# uCAN_Cape.net
KiCad netlist of a schematic drawn in EAGLE
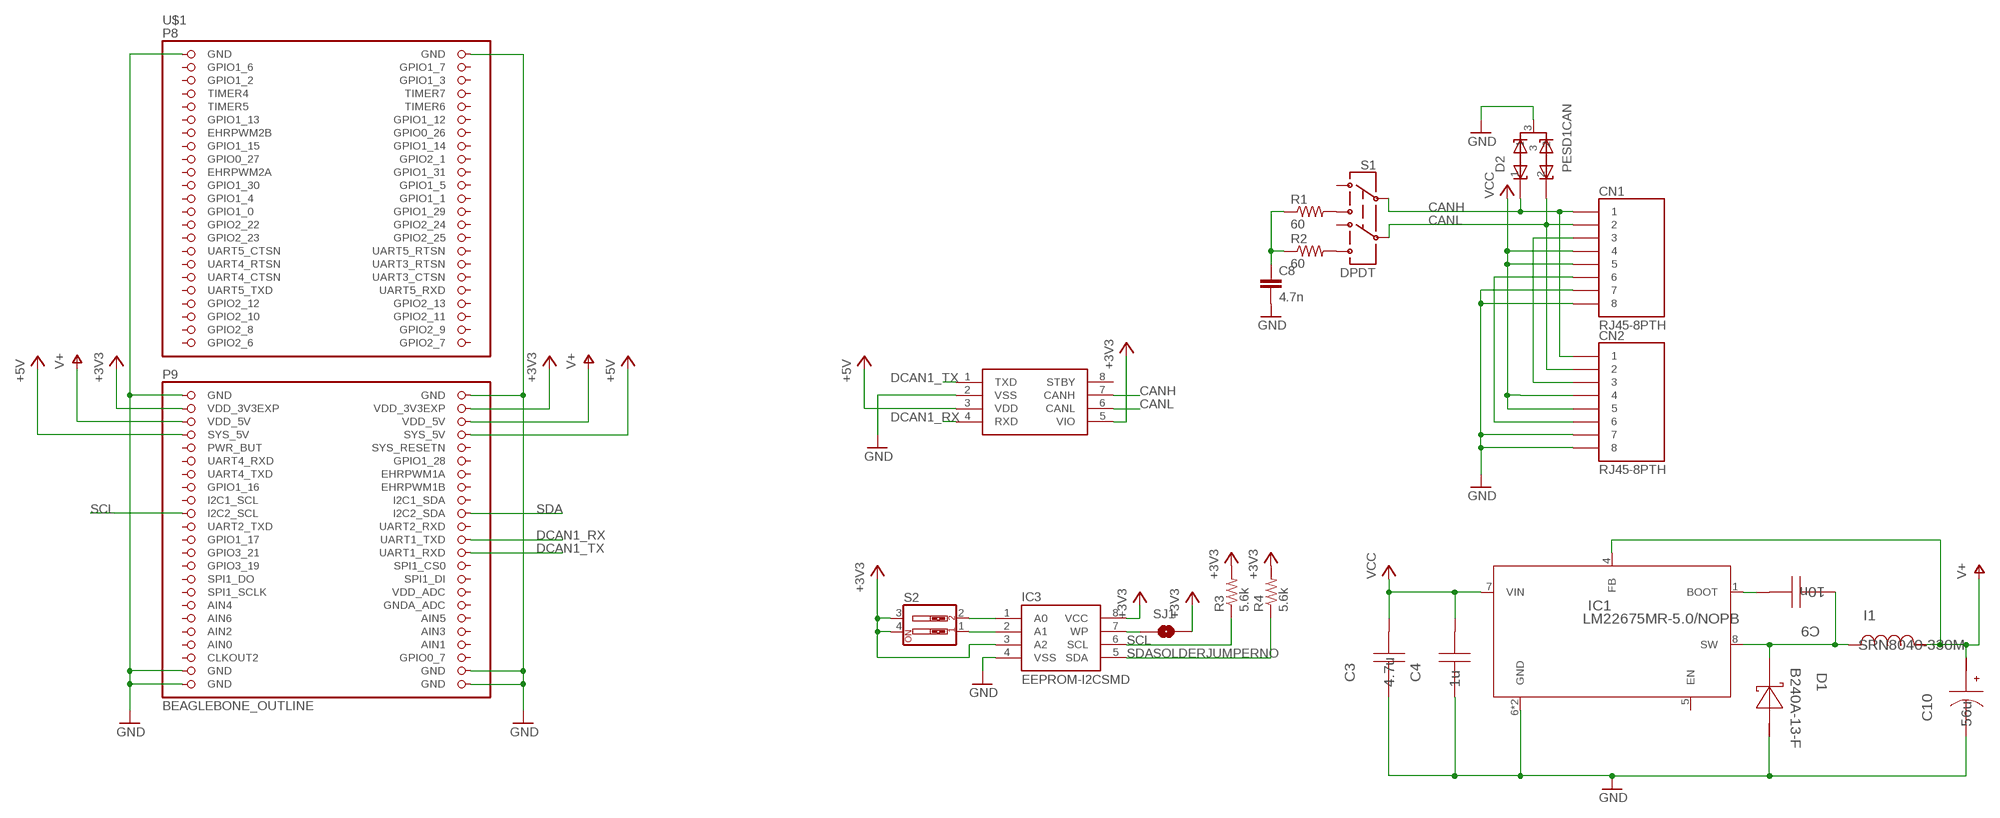
[diagram p0: schematic, sheet 1]

(export (version "E")
  (design (tool "Eeschema 10.0.6"))
  (components
    (comp (ref "C3")
      (value "4.7u")
      (footprint "eagle-import:1206")
      (fields (field (name "MANUFACTURER_PART_NUMBER") "GRM31CR71H475KA12L"))
      (libsource (lib "eagle-import") (part "GRM31CR71H475KA12L"))
    )
    (comp (ref "C4")
      (value "1u")
      (footprint "eagle-import:0805")
      (fields (field (name "MANUFACTURER_PART_NUMBER") "GMK212B7105KG-T"))
      (libsource (lib "eagle-import") (part "GMK212B7105KG-T"))
    )
    (comp (ref "C8")
      (value "4.7n")
      (footprint "eagle-import:0603-CAP")
      (libsource (lib "eagle-import") (part "CAP0603-CAP"))
    )
    (comp (ref "C9")
      (value "10n")
      (footprint "eagle-import:0805")
      (fields (field (name "MANUFACTURER_PART_NUMBER") "C0805C103K5RACTU"))
      (libsource (lib "eagle-import") (part "C0805C103K5RACTU"))
    )
    (comp (ref "C10")
      (value "56u")
      (footprint "eagle-import:SM_RADIAL_6.3AMM")
      (fields (field (name "MANUFACTURER_PART_NUMBER") "10SVP56M"))
      (libsource (lib "eagle-import") (part "10SVP56M"))
    )
    (comp (ref "CN1")
      (value "RJ45-8PTH")
      (footprint "eagle-import:RJ45-8")
      (libsource (lib "eagle-import") (part "RJ45-8PTH"))
    )
    (comp (ref "CN2")
      (value "RJ45-8PTH")
      (footprint "eagle-import:RJ45-8")
      (libsource (lib "eagle-import") (part "RJ45-8PTH"))
    )
    (comp (ref "D1")
      (value "B240A-13-F")
      (footprint "eagle-import:SMA")
      (libsource (lib "eagle-import") (part "B240A-13-F"))
    )
    (comp (ref "D2")
      (value "PESD1CAN")
      (footprint "eagle-import:SOT23")
      (libsource (lib "eagle-import") (part "PESD1CAN"))
    )
    (comp (ref "I1")
      (value "SRN8040-330M")
      (footprint "eagle-import:SRN8040")
      (libsource (lib "eagle-import") (part "SRN8040-330M"))
    )
    (comp (ref "IC1")
      (value "LM22675MR-5.0/NOPB")
      (footprint "eagle-import:MRA08B")
      (libsource (lib "eagle-import") (part "LM22675MR-5.0/NOPB"))
    )
    (comp (ref "IC2")
      (value "MCP2562")
      (footprint "eagle-import:SO08")
      (libsource (lib "eagle-import") (part "MCP2562"))
    )
    (comp (ref "IC3")
      (value "EEPROM-I2CSMD")
      (footprint "eagle-import:SO08")
      (libsource (lib "eagle-import") (part "EEPROM-I2CSMD"))
    )
    (comp (ref "R1")
      (value "60")
      (footprint "eagle-import:0603-RES")
      (libsource (lib "eagle-import") (part "RESISTOR0603-RES"))
    )
    (comp (ref "R2")
      (value "60")
      (footprint "eagle-import:0603-RES")
      (libsource (lib "eagle-import") (part "RESISTOR0603-RES"))
    )
    (comp (ref "R3")
      (value "5.6k")
      (footprint "eagle-import:0603-RES")
      (libsource (lib "eagle-import") (part "RESISTOR0603-RES"))
    )
    (comp (ref "R4")
      (value "5.6k")
      (footprint "eagle-import:0603-RES")
      (libsource (lib "eagle-import") (part "RESISTOR0603-RES"))
    )
    (comp (ref "S1")
      (value "DPDT")
      (footprint "eagle-import:AYZ0202")
      (libsource (lib "eagle-import") (part "SWITCH-DPDTAYZ0202"))
    )
    (comp (ref "S2")
      (value "SW_DIP-2")
      (footprint "eagle-import:DIPSWITCH-02")
      (libsource (lib "eagle-import") (part "SW_DIP-2"))
    )
    (comp (ref "SJ1")
      (value "SOLDERJUMPERNO")
      (footprint "eagle-import:SJ_2S-NO")
      (libsource (lib "eagle-import") (part "SOLDERJUMPERNO"))
    )
    (comp (ref "U$1")
      (value "BEAGLEBONE_OUTLINE")
      (footprint "eagle-import:BEAGLEBONE_SHIELD")
      (libsource (lib "eagle-import") (part "BEAGLEBONE_OUTLINE"))
    )
  )
  (nets
    (net (code "1") (name "+3V3") (class "Default")
      (node (ref "IC2") (pin "5") (pinfunction "VIO_5") (pintype "bidirectional"))
      (node (ref "IC3") (pin "3") (pinfunction "A2_3") (pintype "bidirectional"))
      (node (ref "IC3") (pin "8") (pinfunction "VCC_8") (pintype "power_in"))
      (node (ref "R3") (pin "2") (pinfunction "2_2") (pintype "passive"))
      (node (ref "R4") (pin "2") (pinfunction "2_2") (pintype "passive"))
      (node (ref "S2") (pin "3") (pinfunction "3_3") (pintype "passive"))
      (node (ref "S2") (pin "4") (pinfunction "4_4") (pintype "passive"))
      (node (ref "SJ1") (pin "2") (pinfunction "2_2") (pintype "passive"))
      (node (ref "U$1") (pin "49") (pinfunction "VDD_3V3EXP_49") (pintype "power_in"))
      (node (ref "U$1") (pin "50") (pinfunction "VDD_3V3EXP_50") (pintype "power_in"))
    )
    (net (code "2") (name "+5V") (class "Default")
      (node (ref "IC2") (pin "3") (pinfunction "VDD_3") (pintype "bidirectional"))
      (node (ref "U$1") (pin "53") (pinfunction "SYS_5V_53") (pintype "power_in"))
      (node (ref "U$1") (pin "54") (pinfunction "SYS_5V_54") (pintype "passive"))
    )
    (net (code "3") (name "/AIN0") (class "Default")
      (node (ref "U$1") (pin "85") (pinfunction "AIN0_85") (pintype "power_in"))
    )
    (net (code "4") (name "/CANH") (class "Default")
      (node (ref "CN1") (pin "1") (pinfunction "1_1") (pintype "bidirectional"))
      (node (ref "CN2") (pin "1") (pinfunction "1_1") (pintype "bidirectional"))
      (node (ref "D2") (pin "1") (pinfunction "1_1") (pintype "bidirectional"))
      (node (ref "IC2") (pin "7") (pinfunction "CANH_7") (pintype "bidirectional"))
      (node (ref "S1") (pin "2") (pinfunction "2_2") (pintype "bidirectional"))
    )
    (net (code "5") (name "/CANL") (class "Default")
      (node (ref "CN1") (pin "2") (pinfunction "2_2") (pintype "bidirectional"))
      (node (ref "CN2") (pin "2") (pinfunction "2_2") (pintype "bidirectional"))
      (node (ref "D2") (pin "2") (pinfunction "2_2") (pintype "bidirectional"))
      (node (ref "IC2") (pin "6") (pinfunction "CANL_6") (pintype "bidirectional"))
      (node (ref "S1") (pin "5") (pinfunction "5_5") (pintype "bidirectional"))
    )
    (net (code "6") (name "/DCAN1_RX") (class "Default")
      (node (ref "IC2") (pin "4") (pinfunction "RXD_4") (pintype "bidirectional"))
      (node (ref "U$1") (pin "70") (pinfunction "UART1_TXD_70") (pintype "passive"))
    )
    (net (code "7") (name "/DCAN1_TX") (class "Default")
      (node (ref "IC2") (pin "1") (pinfunction "TXD_1") (pintype "bidirectional"))
      (node (ref "U$1") (pin "72") (pinfunction "UART1_RXD_72") (pintype "passive"))
    )
    (net (code "8") (name "/SCL") (class "Default")
      (node (ref "IC3") (pin "6") (pinfunction "SCL_6") (pintype "bidirectional"))
      (node (ref "R3") (pin "1") (pinfunction "1_1") (pintype "passive"))
      (node (ref "U$1") (pin "65") (pinfunction "I2C2_SCL_65") (pintype "passive"))
    )
    (net (code "9") (name "/SDA") (class "Default")
      (node (ref "IC3") (pin "5") (pinfunction "SDA_5") (pintype "bidirectional"))
      (node (ref "R4") (pin "1") (pinfunction "1_1") (pintype "passive"))
      (node (ref "U$1") (pin "66") (pinfunction "I2C2_SDA_66") (pintype "passive"))
    )
    (net (code "10") (name "GND") (class "Default")
      (node (ref "C10") (pin "2") (pinfunction "-_2") (pintype "passive"))
      (node (ref "C3") (pin "2") (pinfunction "2_2") (pintype "passive"))
      (node (ref "C4") (pin "2") (pinfunction "2_2") (pintype "passive"))
      (node (ref "C8") (pin "2") (pinfunction "2_2") (pintype "passive"))
      (node (ref "CN1") (pin "7") (pinfunction "7_7") (pintype "bidirectional"))
      (node (ref "CN1") (pin "8") (pinfunction "8_8") (pintype "bidirectional"))
      (node (ref "CN2") (pin "7") (pinfunction "7_7") (pintype "bidirectional"))
      (node (ref "CN2") (pin "8") (pinfunction "8_8") (pintype "bidirectional"))
      (node (ref "D1") (pin "2") (pinfunction "A_2") (pintype "passive"))
      (node (ref "D2") (pin "3") (pinfunction "3_3") (pintype "bidirectional"))
      (node (ref "IC1") (pin "6") (pinfunction "GND_6") (pintype "passive"))
      (node (ref "IC1") (pin "EPAD") (pinfunction "GND_EPAD") (pintype "passive"))
      (node (ref "IC2") (pin "2") (pinfunction "VSS_2") (pintype "bidirectional"))
      (node (ref "IC3") (pin "4") (pinfunction "VSS_4") (pintype "power_in"))
      (node (ref "U$1") (pin "1") (pinfunction "GND_1") (pintype "power_in"))
      (node (ref "U$1") (pin "2") (pinfunction "GND_2") (pintype "power_in"))
      (node (ref "U$1") (pin "47") (pinfunction "GND_47") (pintype "power_in"))
      (node (ref "U$1") (pin "48") (pinfunction "GND_48") (pintype "power_in"))
      (node (ref "U$1") (pin "89") (pinfunction "GND_89") (pintype "power_in"))
      (node (ref "U$1") (pin "90") (pinfunction "GND_90") (pintype "power_in"))
      (node (ref "U$1") (pin "91") (pinfunction "GND_91") (pintype "power_in"))
      (node (ref "U$1") (pin "92") (pinfunction "GND_92") (pintype "power_in"))
    )
    (net (code "11") (name "Net-(C8-Pad1)") (class "Default")
      (node (ref "C8") (pin "1") (pinfunction "1_1") (pintype "passive"))
      (node (ref "R1") (pin "1") (pinfunction "1_1") (pintype "passive"))
      (node (ref "R2") (pin "1") (pinfunction "1_1") (pintype "passive"))
    )
    (net (code "12") (name "Net-(CN1-Pad3)") (class "Default")
      (node (ref "CN1") (pin "3") (pinfunction "3_3") (pintype "bidirectional"))
      (node (ref "CN2") (pin "3") (pinfunction "3_3") (pintype "bidirectional"))
    )
    (net (code "13") (name "Net-(CN1-Pad6)") (class "Default")
      (node (ref "CN1") (pin "6") (pinfunction "6_6") (pintype "bidirectional"))
      (node (ref "CN2") (pin "6") (pinfunction "6_6") (pintype "bidirectional"))
    )
    (net (code "14") (name "Net-(D1-K)") (class "Default")
      (node (ref "C9") (pin "2") (pinfunction "2_2") (pintype "passive"))
      (node (ref "D1") (pin "1") (pinfunction "K_1") (pintype "passive"))
      (node (ref "I1") (pin "2") (pinfunction "2_2") (pintype "passive"))
      (node (ref "IC1") (pin "8") (pinfunction "SW_8") (pintype "passive"))
    )
    (net (code "15") (name "Net-(IC1-BOOT)") (class "Default")
      (node (ref "C9") (pin "1") (pinfunction "1_1") (pintype "passive"))
      (node (ref "IC1") (pin "1") (pinfunction "BOOT_1") (pintype "passive"))
    )
    (net (code "16") (name "Net-(IC3-A0)") (class "Default")
      (node (ref "IC3") (pin "1") (pinfunction "A0_1") (pintype "bidirectional"))
      (node (ref "S2") (pin "2") (pinfunction "2_2") (pintype "passive"))
    )
    (net (code "17") (name "Net-(IC3-A1)") (class "Default")
      (node (ref "IC3") (pin "2") (pinfunction "A1_2") (pintype "bidirectional"))
      (node (ref "S2") (pin "1") (pinfunction "1_1") (pintype "passive"))
    )
    (net (code "18") (name "Net-(IC3-WP)") (class "Default")
      (node (ref "IC3") (pin "7") (pinfunction "WP_7") (pintype "bidirectional"))
      (node (ref "SJ1") (pin "1") (pinfunction "1_1") (pintype "passive"))
    )
    (net (code "19") (name "Net-(R1-Pad2)") (class "Default")
      (node (ref "R1") (pin "2") (pinfunction "2_2") (pintype "passive"))
      (node (ref "S1") (pin "3") (pinfunction "3_3") (pintype "bidirectional"))
    )
    (net (code "20") (name "Net-(R2-Pad2)") (class "Default")
      (node (ref "R2") (pin "2") (pinfunction "2_2") (pintype "passive"))
      (node (ref "S1") (pin "6") (pinfunction "6_6") (pintype "bidirectional"))
    )
    (net (code "21") (name "V+") (class "Default")
      (node (ref "C10") (pin "1") (pinfunction "+_1") (pintype "passive"))
      (node (ref "I1") (pin "1") (pinfunction "1_1") (pintype "passive"))
      (node (ref "IC1") (pin "4") (pinfunction "FB_4") (pintype "passive"))
      (node (ref "U$1") (pin "51") (pinfunction "VDD_5V_51") (pintype "power_in"))
      (node (ref "U$1") (pin "52") (pinfunction "VDD_5V_52") (pintype "power_in"))
    )
    (net (code "22") (name "VCC") (class "Default")
      (node (ref "C3") (pin "1") (pinfunction "1_1") (pintype "passive"))
      (node (ref "C4") (pin "1") (pinfunction "1_1") (pintype "passive"))
      (node (ref "CN1") (pin "4") (pinfunction "4_4") (pintype "bidirectional"))
      (node (ref "CN1") (pin "5") (pinfunction "5_5") (pintype "bidirectional"))
      (node (ref "CN2") (pin "4") (pinfunction "4_4") (pintype "bidirectional"))
      (node (ref "CN2") (pin "5") (pinfunction "5_5") (pintype "bidirectional"))
      (node (ref "IC1") (pin "7") (pinfunction "VIN_7") (pintype "passive"))
    )
    (net (code "23") (name "unconnected-(IC1-EN-Pad5)") (class "Default")
      (node (ref "IC1") (pin "5") (pinfunction "EN_5") (pintype "passive"))
    )
    (net (code "24") (name "unconnected-(IC2-STBY-Pad8)") (class "Default")
      (node (ref "IC2") (pin "8") (pinfunction "STBY_8") (pintype "bidirectional"))
    )
    (net (code "25") (name "unconnected-(S1-Pad1)") (class "Default")
      (node (ref "S1") (pin "1") (pinfunction "1_1") (pintype "bidirectional"))
    )
    (net (code "26") (name "unconnected-(S1-Pad4)") (class "Default")
      (node (ref "S1") (pin "4") (pinfunction "4_4") (pintype "bidirectional"))
    )
    (net (code "27") (name "unconnected-(U$1-AIN1-Pad86)") (class "Default")
      (node (ref "U$1") (pin "86") (pinfunction "AIN1_86") (pintype "passive"))
    )
    (net (code "28") (name "unconnected-(U$1-AIN2-Pad83)") (class "Default")
      (node (ref "U$1") (pin "83") (pinfunction "AIN2_83") (pintype "passive"))
    )
    (net (code "29") (name "unconnected-(U$1-AIN3-Pad84)") (class "Default")
      (node (ref "U$1") (pin "84") (pinfunction "AIN3_84") (pintype "passive"))
    )
    (net (code "30") (name "unconnected-(U$1-AIN4-Pad79)") (class "Default")
      (node (ref "U$1") (pin "79") (pinfunction "AIN4_79") (pintype "passive"))
    )
    (net (code "31") (name "unconnected-(U$1-AIN5-Pad82)") (class "Default")
      (node (ref "U$1") (pin "82") (pinfunction "AIN5_82") (pintype "passive"))
    )
    (net (code "32") (name "unconnected-(U$1-AIN6-Pad81)") (class "Default")
      (node (ref "U$1") (pin "81") (pinfunction "AIN6_81") (pintype "passive"))
    )
    (net (code "33") (name "unconnected-(U$1-CLKOUT2-Pad87)") (class "Default")
      (node (ref "U$1") (pin "87") (pinfunction "CLKOUT2_87") (pintype "input"))
    )
    (net (code "34") (name "unconnected-(U$1-EHRPWM1A-Pad60)") (class "Default")
      (node (ref "U$1") (pin "60") (pinfunction "EHRPWM1A_60") (pintype "passive"))
    )
    (net (code "35") (name "unconnected-(U$1-EHRPWM1B-Pad62)") (class "Default")
      (node (ref "U$1") (pin "62") (pinfunction "EHRPWM1B_62") (pintype "passive"))
    )
    (net (code "36") (name "unconnected-(U$1-EHRPWM2A-Pad19)") (class "Default")
      (node (ref "U$1") (pin "19") (pinfunction "EHRPWM2A_19") (pintype "passive"))
    )
    (net (code "37") (name "unconnected-(U$1-EHRPWM2B-Pad13)") (class "Default")
      (node (ref "U$1") (pin "13") (pinfunction "EHRPWM2B_13") (pintype "passive"))
    )
    (net (code "38") (name "unconnected-(U$1-GNDA_ADC-Pad80)") (class "Default")
      (node (ref "U$1") (pin "80") (pinfunction "GNDA_ADC_80") (pintype "passive"))
    )
    (net (code "39") (name "unconnected-(U$1-GPIO0_7-Pad88)") (class "Default")
      (node (ref "U$1") (pin "88") (pinfunction "GPIO0_7_88") (pintype "passive"))
    )
    (net (code "40") (name "unconnected-(U$1-GPIO0_26-Pad14)") (class "Default")
      (node (ref "U$1") (pin "14") (pinfunction "GPIO0_26_14") (pintype "passive"))
    )
    (net (code "41") (name "unconnected-(U$1-GPIO0_27-Pad17)") (class "Default")
      (node (ref "U$1") (pin "17") (pinfunction "GPIO0_27_17") (pintype "passive"))
    )
    (net (code "42") (name "unconnected-(U$1-GPIO1_0-Pad25)") (class "Default")
      (node (ref "U$1") (pin "25") (pinfunction "GPIO1_0_25") (pintype "passive"))
    )
    (net (code "43") (name "unconnected-(U$1-GPIO1_1-Pad24)") (class "Default")
      (node (ref "U$1") (pin "24") (pinfunction "GPIO1_1_24") (pintype "passive"))
    )
    (net (code "44") (name "unconnected-(U$1-GPIO1_2-Pad5)") (class "Default")
      (node (ref "U$1") (pin "5") (pinfunction "GPIO1_2_5") (pintype "passive"))
    )
    (net (code "45") (name "unconnected-(U$1-GPIO1_3-Pad6)") (class "Default")
      (node (ref "U$1") (pin "6") (pinfunction "GPIO1_3_6") (pintype "passive"))
    )
    (net (code "46") (name "unconnected-(U$1-GPIO1_4-Pad23)") (class "Default")
      (node (ref "U$1") (pin "23") (pinfunction "GPIO1_4_23") (pintype "passive"))
    )
    (net (code "47") (name "unconnected-(U$1-GPIO1_5-Pad22)") (class "Default")
      (node (ref "U$1") (pin "22") (pinfunction "GPIO1_5_22") (pintype "passive"))
    )
    (net (code "48") (name "unconnected-(U$1-GPIO1_6-Pad3)") (class "Default")
      (node (ref "U$1") (pin "3") (pinfunction "GPIO1_6_3") (pintype "passive"))
    )
    (net (code "49") (name "unconnected-(U$1-GPIO1_7-Pad4)") (class "Default")
      (node (ref "U$1") (pin "4") (pinfunction "GPIO1_7_4") (pintype "passive"))
    )
    (net (code "50") (name "unconnected-(U$1-GPIO1_12-Pad12)") (class "Default")
      (node (ref "U$1") (pin "12") (pinfunction "GPIO1_12_12") (pintype "passive"))
    )
    (net (code "51") (name "unconnected-(U$1-GPIO1_13-Pad11)") (class "Default")
      (node (ref "U$1") (pin "11") (pinfunction "GPIO1_13_11") (pintype "passive"))
    )
    (net (code "52") (name "unconnected-(U$1-GPIO1_14-Pad16)") (class "Default")
      (node (ref "U$1") (pin "16") (pinfunction "GPIO1_14_16") (pintype "passive"))
    )
    (net (code "53") (name "unconnected-(U$1-GPIO1_15-Pad15)") (class "Default")
      (node (ref "U$1") (pin "15") (pinfunction "GPIO1_15_15") (pintype "passive"))
    )
    (net (code "54") (name "unconnected-(U$1-GPIO1_16-Pad61)") (class "Default")
      (node (ref "U$1") (pin "61") (pinfunction "GPIO1_16_61") (pintype "passive"))
    )
    (net (code "55") (name "unconnected-(U$1-GPIO1_17-Pad69)") (class "Default")
      (node (ref "U$1") (pin "69") (pinfunction "GPIO1_17_69") (pintype "passive"))
    )
    (net (code "56") (name "unconnected-(U$1-GPIO1_28-Pad58)") (class "Default")
      (node (ref "U$1") (pin "58") (pinfunction "GPIO1_28_58") (pintype "passive"))
    )
    (net (code "57") (name "unconnected-(U$1-GPIO1_29-Pad26)") (class "Default")
      (node (ref "U$1") (pin "26") (pinfunction "GPIO1_29_26") (pintype "passive"))
    )
    (net (code "58") (name "unconnected-(U$1-GPIO1_30-Pad21)") (class "Default")
      (node (ref "U$1") (pin "21") (pinfunction "GPIO1_30_21") (pintype "passive"))
    )
    (net (code "59") (name "unconnected-(U$1-GPIO1_31-Pad20)") (class "Default")
      (node (ref "U$1") (pin "20") (pinfunction "GPIO1_31_20") (pintype "passive"))
    )
    (net (code "60") (name "unconnected-(U$1-GPIO2_1-Pad18)") (class "Default")
      (node (ref "U$1") (pin "18") (pinfunction "GPIO2_1_18") (pintype "passive"))
    )
    (net (code "61") (name "unconnected-(U$1-GPIO2_6-Pad45)") (class "Default")
      (node (ref "U$1") (pin "45") (pinfunction "GPIO2_6_45") (pintype "passive"))
    )
    (net (code "62") (name "unconnected-(U$1-GPIO2_7-Pad46)") (class "Default")
      (node (ref "U$1") (pin "46") (pinfunction "GPIO2_7_46") (pintype "passive"))
    )
    (net (code "63") (name "unconnected-(U$1-GPIO2_8-Pad43)") (class "Default")
      (node (ref "U$1") (pin "43") (pinfunction "GPIO2_8_43") (pintype "passive"))
    )
    (net (code "64") (name "unconnected-(U$1-GPIO2_9-Pad44)") (class "Default")
      (node (ref "U$1") (pin "44") (pinfunction "GPIO2_9_44") (pintype "passive"))
    )
    (net (code "65") (name "unconnected-(U$1-GPIO2_10-Pad41)") (class "Default")
      (node (ref "U$1") (pin "41") (pinfunction "GPIO2_10_41") (pintype "passive"))
    )
    (net (code "66") (name "unconnected-(U$1-GPIO2_11-Pad42)") (class "Default")
      (node (ref "U$1") (pin "42") (pinfunction "GPIO2_11_42") (pintype "passive"))
    )
    (net (code "67") (name "unconnected-(U$1-GPIO2_12-Pad39)") (class "Default")
      (node (ref "U$1") (pin "39") (pinfunction "GPIO2_12_39") (pintype "passive"))
    )
    (net (code "68") (name "unconnected-(U$1-GPIO2_13-Pad40)") (class "Default")
      (node (ref "U$1") (pin "40") (pinfunction "GPIO2_13_40") (pintype "passive"))
    )
    (net (code "69") (name "unconnected-(U$1-GPIO2_22-Pad27)") (class "Default")
      (node (ref "U$1") (pin "27") (pinfunction "GPIO2_22_27") (pintype "passive"))
    )
    (net (code "70") (name "unconnected-(U$1-GPIO2_23-Pad29)") (class "Default")
      (node (ref "U$1") (pin "29") (pinfunction "GPIO2_23_29") (pintype "passive"))
    )
    (net (code "71") (name "unconnected-(U$1-GPIO2_24-Pad28)") (class "Default")
      (node (ref "U$1") (pin "28") (pinfunction "GPIO2_24_28") (pintype "passive"))
    )
    (net (code "72") (name "unconnected-(U$1-GPIO2_25-Pad30)") (class "Default")
      (node (ref "U$1") (pin "30") (pinfunction "GPIO2_25_30") (pintype "passive"))
    )
    (net (code "73") (name "unconnected-(U$1-GPIO3_19-Pad73)") (class "Default")
      (node (ref "U$1") (pin "73") (pinfunction "GPIO3_19_73") (pintype "passive"))
    )
    (net (code "74") (name "unconnected-(U$1-GPIO3_21-Pad71)") (class "Default")
      (node (ref "U$1") (pin "71") (pinfunction "GPIO3_21_71") (pintype "passive"))
    )
    (net (code "75") (name "unconnected-(U$1-I2C1_SCL-Pad63)") (class "Default")
      (node (ref "U$1") (pin "63") (pinfunction "I2C1_SCL_63") (pintype "passive"))
    )
    (net (code "76") (name "unconnected-(U$1-I2C1_SDA-Pad64)") (class "Default")
      (node (ref "U$1") (pin "64") (pinfunction "I2C1_SDA_64") (pintype "passive"))
    )
    (net (code "77") (name "unconnected-(U$1-PWR_BUT-Pad55)") (class "Default")
      (node (ref "U$1") (pin "55") (pinfunction "PWR_BUT_55") (pintype "passive"))
    )
    (net (code "78") (name "unconnected-(U$1-SPI1_CS0-Pad74)") (class "Default")
      (node (ref "U$1") (pin "74") (pinfunction "SPI1_CS0_74") (pintype "passive"))
    )
    (net (code "79") (name "unconnected-(U$1-SPI1_DI-Pad76)") (class "Default")
      (node (ref "U$1") (pin "76") (pinfunction "SPI1_DI_76") (pintype "passive"))
    )
    (net (code "80") (name "unconnected-(U$1-SPI1_DO-Pad75)") (class "Default")
      (node (ref "U$1") (pin "75") (pinfunction "SPI1_DO_75") (pintype "passive"))
    )
    (net (code "81") (name "unconnected-(U$1-SPI1_SCLK-Pad77)") (class "Default")
      (node (ref "U$1") (pin "77") (pinfunction "SPI1_SCLK_77") (pintype "passive"))
    )
    (net (code "82") (name "unconnected-(U$1-SYS_RESETN-Pad56)") (class "Default")
      (node (ref "U$1") (pin "56") (pinfunction "SYS_RESETN_56") (pintype "passive"))
    )
    (net (code "83") (name "unconnected-(U$1-TIMER4-Pad7)") (class "Default")
      (node (ref "U$1") (pin "7") (pinfunction "TIMER4_7") (pintype "passive"))
    )
    (net (code "84") (name "unconnected-(U$1-TIMER5-Pad9)") (class "Default")
      (node (ref "U$1") (pin "9") (pinfunction "TIMER5_9") (pintype "passive"))
    )
    (net (code "85") (name "unconnected-(U$1-TIMER6-Pad10)") (class "Default")
      (node (ref "U$1") (pin "10") (pinfunction "TIMER6_10") (pintype "passive"))
    )
    (net (code "86") (name "unconnected-(U$1-TIMER7-Pad8)") (class "Default")
      (node (ref "U$1") (pin "8") (pinfunction "TIMER7_8") (pintype "passive"))
    )
    (net (code "87") (name "unconnected-(U$1-UART2_RXD-Pad68)") (class "Default")
      (node (ref "U$1") (pin "68") (pinfunction "UART2_RXD_68") (pintype "passive"))
    )
    (net (code "88") (name "unconnected-(U$1-UART2_TXD-Pad67)") (class "Default")
      (node (ref "U$1") (pin "67") (pinfunction "UART2_TXD_67") (pintype "passive"))
    )
    (net (code "89") (name "unconnected-(U$1-UART3_CTSN-Pad36)") (class "Default")
      (node (ref "U$1") (pin "36") (pinfunction "UART3_CTSN_36") (pintype "passive"))
    )
    (net (code "90") (name "unconnected-(U$1-UART3_RTSN-Pad34)") (class "Default")
      (node (ref "U$1") (pin "34") (pinfunction "UART3_RTSN_34") (pintype "passive"))
    )
    (net (code "91") (name "unconnected-(U$1-UART4_CTSN-Pad35)") (class "Default")
      (node (ref "U$1") (pin "35") (pinfunction "UART4_CTSN_35") (pintype "passive"))
    )
    (net (code "92") (name "unconnected-(U$1-UART4_RTSN-Pad33)") (class "Default")
      (node (ref "U$1") (pin "33") (pinfunction "UART4_RTSN_33") (pintype "passive"))
    )
    (net (code "93") (name "unconnected-(U$1-UART4_RXD-Pad57)") (class "Default")
      (node (ref "U$1") (pin "57") (pinfunction "UART4_RXD_57") (pintype "passive"))
    )
    (net (code "94") (name "unconnected-(U$1-UART4_TXD-Pad59)") (class "Default")
      (node (ref "U$1") (pin "59") (pinfunction "UART4_TXD_59") (pintype "passive"))
    )
    (net (code "95") (name "unconnected-(U$1-UART5_CTSN-Pad31)") (class "Default")
      (node (ref "U$1") (pin "31") (pinfunction "UART5_CTSN_31") (pintype "passive"))
    )
    (net (code "96") (name "unconnected-(U$1-UART5_RTSN-Pad32)") (class "Default")
      (node (ref "U$1") (pin "32") (pinfunction "UART5_RTSN_32") (pintype "passive"))
    )
    (net (code "97") (name "unconnected-(U$1-UART5_RXD-Pad38)") (class "Default")
      (node (ref "U$1") (pin "38") (pinfunction "UART5_RXD_38") (pintype "passive"))
    )
    (net (code "98") (name "unconnected-(U$1-UART5_TXD-Pad37)") (class "Default")
      (node (ref "U$1") (pin "37") (pinfunction "UART5_TXD_37") (pintype "passive"))
    )
    (net (code "99") (name "unconnected-(U$1-VDD_ADC-Pad78)") (class "Default")
      (node (ref "U$1") (pin "78") (pinfunction "VDD_ADC_78") (pintype "passive"))
    )
  )
)
